# Prac_FabLab.net
KiCad netlist of a schematic drawn in Altium Designer
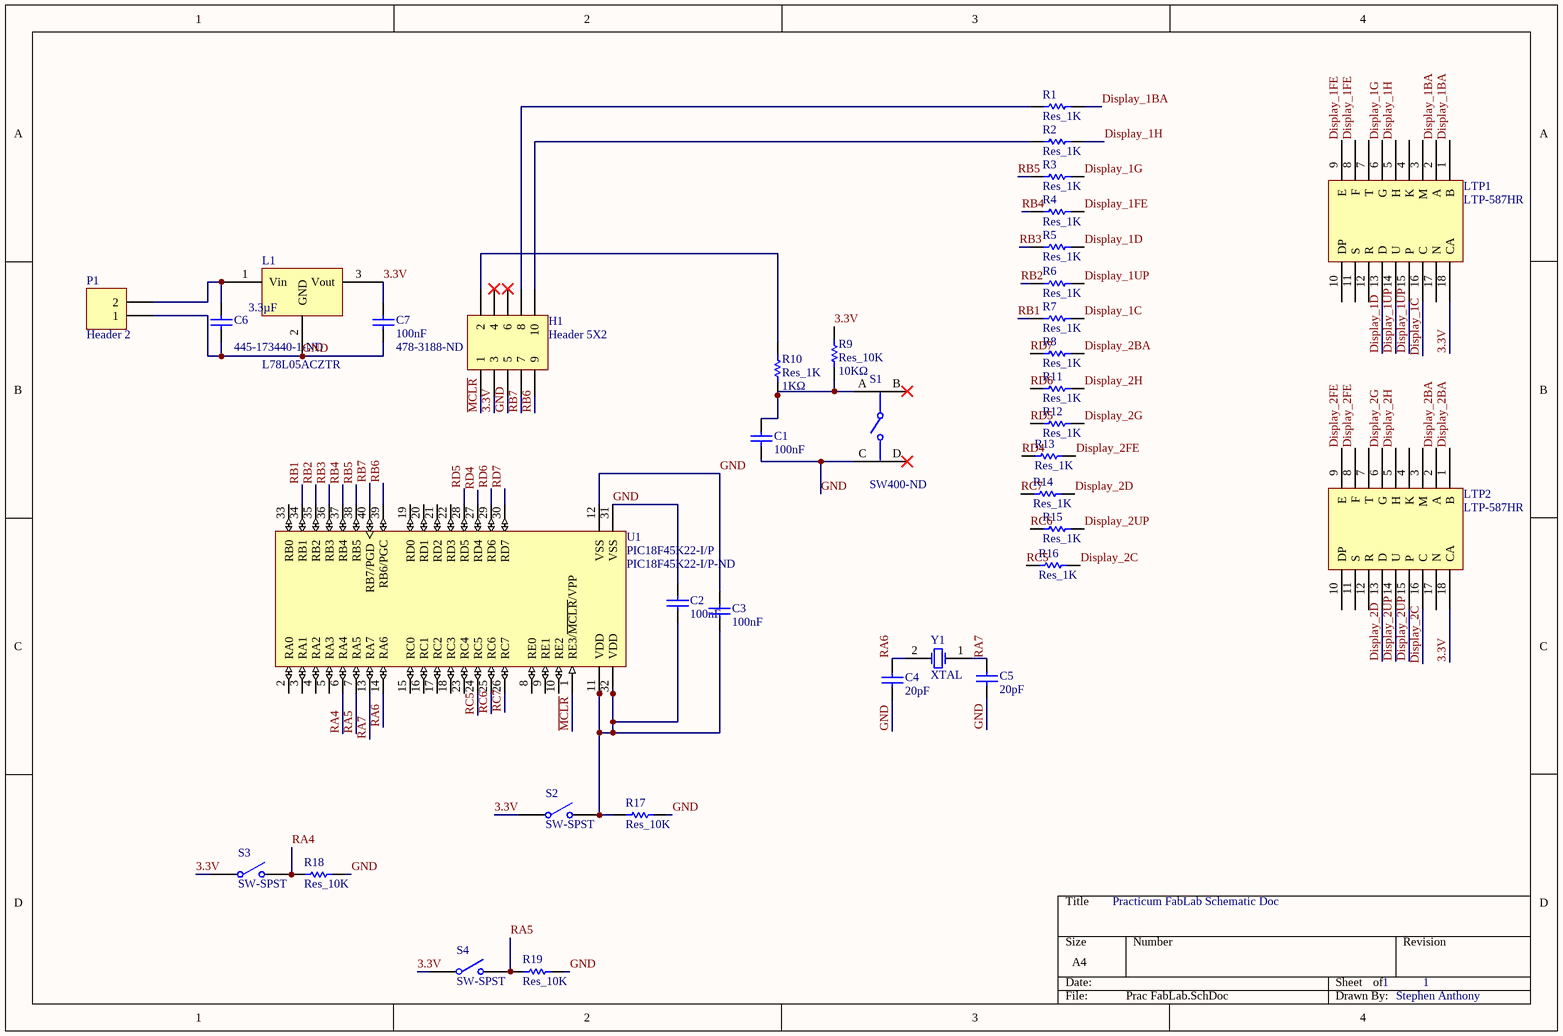
[diagram p0: Prac FabLab.SchDoc]

(export (version "E")
  (design (tool "Eeschema 10.0.6"))
  (components
    (comp (ref "C1")
      (value "100nF")
      (footprint "RADIAL_0.2")
      (description "Capacitor")
      (fields (field (name "Comment") "CAP_100nF") (field (name "PUBLISHER") "Altium Limited"))
      (libsource (lib "Schematic Components") (part "CAP_100nF"))
    )
    (comp (ref "C2")
      (value "100nF")
      (footprint "RADIAL_0.2")
      (description "Capacitor")
      (fields (field (name "Comment") "CAP_100nF") (field (name "PUBLISHER") "Altium Limited"))
      (libsource (lib "Schematic Components") (part "CAP_100nF"))
    )
    (comp (ref "C3")
      (value "100nF")
      (footprint "RADIAL_0.2")
      (description "Capacitor")
      (fields (field (name "Comment") "CAP_100nF") (field (name "PUBLISHER") "Altium Limited"))
      (libsource (lib "Schematic Components") (part "CAP_100nF"))
    )
    (comp (ref "C4")
      (value "20pF")
      (footprint "RADIAL_0.2")
      (description "Capacitor")
      (fields (field (name "PUBLISHER") "Altium Limited"))
      (libsource (lib "Patient Alarm System Altium Integrated Library of Components") (part "Capacitor"))
    )
    (comp (ref "C5")
      (value "20pF")
      (footprint "RADIAL_0.2")
      (description "Capacitor")
      (fields (field (name "PUBLISHER") "Altium Limited"))
      (libsource (lib "Patient Alarm System Altium Integrated Library of Components") (part "Capacitor"))
    )
    (comp (ref "C6")
      (value "3.3µF")
      (footprint "AXIAL_0.2")
      (description "Capacitor")
      (fields
        (field (name "SUPPLIER PART NUMBER 1") "445-173440-1-ND")
        (field (name "Comment") "CAP_3.3µF")
        (field (name "PUBLISHER") "Altium Limited")
      )
      (libsource (lib "Patient Alarm System Altium Integrated Library of Components") (part "CAP_3.3µF"))
    )
    (comp (ref "C7")
      (value "100nF")
      (footprint "AXIAL_0.2")
      (description "Capacitor")
      (fields
        (field (name "SUPPLIER PART NUMBER 1") "478-3188-ND")
        (field (name "Comment") "CAP_100nF")
        (field (name "PUBLISHER") "Altium Limited")
      )
      (libsource (lib "Patient Alarm System Altium Integrated Library of Components") (part "CAP_100nF"))
    )
    (comp (ref "H1")
      (value "Header 5X2")
      (footprint "HDR2X5")
      (description "Header, 5-Pin, Dual row")
      (fields (field (name "PUBLISHER") "Altium Limited"))
      (libsource (lib "Miscellaneous Connectors") (part "Header 5X2"))
    )
    (comp (ref "L1")
      (value "L78L05ACZTR")
      (footprint "TO-220-AB")
      (libsource (lib "Patient Alarm System Altium Integrated Library of Components") (part "L78L05ACZTR"))
    )
    (comp (ref "LTP1")
      (value "LTP-587HR")
      (footprint "LTP-587HR_DIP18")
      (libsource (lib "Patient Alarm System Altium Integrated Library of Components") (part "LTP-587HR"))
    )
    (comp (ref "LTP2")
      (value "LTP-587HR")
      (footprint "LTP-587HR_DIP18")
      (libsource (lib "Patient Alarm System Altium Integrated Library of Components") (part "LTP-587HR"))
    )
    (comp (ref "P1")
      (value "Header 2")
      (footprint "HDR1X2")
      (description "Header, 2-Pin")
      (fields (field (name "PUBLISHER") "Altium Limited"))
      (libsource (lib "Miscellaneous Connectors") (part "Header 2"))
    )
    (comp (ref "R1")
      (value "Res_1K")
      (footprint "AXIAL-0.3")
      (description "1 kOhms ±1% 0.25W, 1/4W Through Hole Resistor Axial Flame Retardant Coating, Safety Metal Film")
      (fields (field (name "PUBLISHER") "Altium Limited"))
      (libsource (lib "Patient Alarm System Altium Integrated Library of Components") (part "Res_1K"))
    )
    (comp (ref "R2")
      (value "Res_1K")
      (footprint "AXIAL-0.3")
      (description "1 kOhms ±1% 0.25W, 1/4W Through Hole Resistor Axial Flame Retardant Coating, Safety Metal Film")
      (fields (field (name "PUBLISHER") "Altium Limited"))
      (libsource (lib "Patient Alarm System Altium Integrated Library of Components") (part "Res_1K"))
    )
    (comp (ref "R3")
      (value "Res_1K")
      (footprint "AXIAL-0.3")
      (description "1 kOhms ±1% 0.25W, 1/4W Through Hole Resistor Axial Flame Retardant Coating, Safety Metal Film")
      (fields (field (name "PUBLISHER") "Altium Limited"))
      (libsource (lib "Patient Alarm System Altium Integrated Library of Components") (part "Res_1K"))
    )
    (comp (ref "R4")
      (value "Res_1K")
      (footprint "AXIAL-0.3")
      (description "1 kOhms ±1% 0.25W, 1/4W Through Hole Resistor Axial Flame Retardant Coating, Safety Metal Film")
      (fields (field (name "PUBLISHER") "Altium Limited"))
      (libsource (lib "Patient Alarm System Altium Integrated Library of Components") (part "Res_1K"))
    )
    (comp (ref "R5")
      (value "Res_1K")
      (footprint "AXIAL-0.3")
      (description "1 kOhms ±1% 0.25W, 1/4W Through Hole Resistor Axial Flame Retardant Coating, Safety Metal Film")
      (fields (field (name "PUBLISHER") "Altium Limited"))
      (libsource (lib "Patient Alarm System Altium Integrated Library of Components") (part "Res_1K"))
    )
    (comp (ref "R6")
      (value "Res_1K")
      (footprint "AXIAL-0.3")
      (description "1 kOhms ±1% 0.25W, 1/4W Through Hole Resistor Axial Flame Retardant Coating, Safety Metal Film")
      (fields (field (name "PUBLISHER") "Altium Limited"))
      (libsource (lib "Patient Alarm System Altium Integrated Library of Components") (part "Res_1K"))
    )
    (comp (ref "R7")
      (value "Res_1K")
      (footprint "AXIAL-0.3")
      (description "1 kOhms ±1% 0.25W, 1/4W Through Hole Resistor Axial Flame Retardant Coating, Safety Metal Film")
      (fields (field (name "PUBLISHER") "Altium Limited"))
      (libsource (lib "Patient Alarm System Altium Integrated Library of Components") (part "Res_1K"))
    )
    (comp (ref "R8")
      (value "Res_1K")
      (footprint "AXIAL-0.3")
      (description "1 kOhms ±1% 0.25W, 1/4W Through Hole Resistor Axial Flame Retardant Coating, Safety Metal Film")
      (fields (field (name "PUBLISHER") "Altium Limited"))
      (libsource (lib "Patient Alarm System Altium Integrated Library of Components") (part "Res_1K"))
    )
    (comp (ref "R9")
      (value "Res_10K")
      (footprint "AXIAL-0.3")
      (description "10 kOhms ±1% 0.25W, 1/4W Through Hole Resistor Axial Flame Retardant Coating, Safety Metal Film")
      (fields (field (name "ALTIUM_VALUE") "10KΩ") (field (name "PUBLISHER") "Altium Limited"))
      (libsource (lib "Schematic Components") (part "Res_10K"))
    )
    (comp (ref "R10")
      (value "Res_1K")
      (footprint "AXIAL-0.3")
      (description "1 kOhms ±1% 0.25W, 1/4W Through Hole Resistor Axial Flame Retardant Coating, Safety Metal Film")
      (fields (field (name "ALTIUM_VALUE") "1KΩ") (field (name "PUBLISHER") "Altium Limited"))
      (libsource (lib "Schematic Components") (part "Res_1K"))
    )
    (comp (ref "R11")
      (value "Res_1K")
      (footprint "AXIAL-0.3")
      (description "1 kOhms ±1% 0.25W, 1/4W Through Hole Resistor Axial Flame Retardant Coating, Safety Metal Film")
      (fields (field (name "PUBLISHER") "Altium Limited"))
      (libsource (lib "Patient Alarm System Altium Integrated Library of Components") (part "Res_1K"))
    )
    (comp (ref "R12")
      (value "Res_1K")
      (footprint "AXIAL-0.3")
      (description "1 kOhms ±1% 0.25W, 1/4W Through Hole Resistor Axial Flame Retardant Coating, Safety Metal Film")
      (fields (field (name "PUBLISHER") "Altium Limited"))
      (libsource (lib "Patient Alarm System Altium Integrated Library of Components") (part "Res_1K"))
    )
    (comp (ref "R13")
      (value "Res_1K")
      (footprint "AXIAL-0.3")
      (description "1 kOhms ±1% 0.25W, 1/4W Through Hole Resistor Axial Flame Retardant Coating, Safety Metal Film")
      (fields (field (name "PUBLISHER") "Altium Limited"))
      (libsource (lib "Patient Alarm System Altium Integrated Library of Components") (part "Res_1K"))
    )
    (comp (ref "R14")
      (value "Res_1K")
      (footprint "AXIAL-0.3")
      (description "1 kOhms ±1% 0.25W, 1/4W Through Hole Resistor Axial Flame Retardant Coating, Safety Metal Film")
      (fields (field (name "PUBLISHER") "Altium Limited"))
      (libsource (lib "Patient Alarm System Altium Integrated Library of Components") (part "Res_1K"))
    )
    (comp (ref "R15")
      (value "Res_1K")
      (footprint "AXIAL-0.3")
      (description "1 kOhms ±1% 0.25W, 1/4W Through Hole Resistor Axial Flame Retardant Coating, Safety Metal Film")
      (fields (field (name "PUBLISHER") "Altium Limited"))
      (libsource (lib "Patient Alarm System Altium Integrated Library of Components") (part "Res_1K"))
    )
    (comp (ref "R16")
      (value "Res_1K")
      (footprint "AXIAL-0.3")
      (description "1 kOhms ±1% 0.25W, 1/4W Through Hole Resistor Axial Flame Retardant Coating, Safety Metal Film")
      (fields (field (name "PUBLISHER") "Altium Limited"))
      (libsource (lib "Patient Alarm System Altium Integrated Library of Components") (part "Res_1K"))
    )
    (comp (ref "R17")
      (value "Res_10K")
      (footprint "AXIAL-0.3")
      (description "1 kOhms ±1% 0.25W, 1/4W Through Hole Resistor Axial Flame Retardant Coating, Safety Metal Film")
      (fields (field (name "PUBLISHER") "Altium Limited"))
      (libsource (lib "Patient Alarm System Altium Integrated Library of Components") (part "Res_1K"))
    )
    (comp (ref "R18")
      (value "Res_10K")
      (footprint "AXIAL-0.3")
      (description "1 kOhms ±1% 0.25W, 1/4W Through Hole Resistor Axial Flame Retardant Coating, Safety Metal Film")
      (fields (field (name "PUBLISHER") "Altium Limited"))
      (libsource (lib "Patient Alarm System Altium Integrated Library of Components") (part "Res_1K"))
    )
    (comp (ref "R19")
      (value "Res_10K")
      (footprint "AXIAL-0.3")
      (description "1 kOhms ±1% 0.25W, 1/4W Through Hole Resistor Axial Flame Retardant Coating, Safety Metal Film")
      (fields (field (name "PUBLISHER") "Altium Limited"))
      (libsource (lib "Patient Alarm System Altium Integrated Library of Components") (part "Res_1K"))
    )
    (comp (ref "S1")
      (value "~")
      (footprint "SW-SPST-1")
      (description "Tactile Switch SPST-NO Top Actuated Through Hole")
      (fields (field (name "SUPPLIER PART NUMBER 1") "SW400-ND") (field (name "PUBLISHER") "Altium Limited"))
      (libsource (lib "Schematic Components") (part "SW-SPST_B3F-1000"))
    )
    (comp (ref "S2")
      (value "SW-SPST")
      (footprint "SPST-2")
      (description "Single-Pole, Single-Throw Switch")
      (fields (field (name "PUBLISHER") "Altium Limited"))
      (libsource (lib "Miscellaneous Devices") (part "SW-SPST"))
    )
    (comp (ref "S3")
      (value "SW-SPST")
      (footprint "SPST-2")
      (description "Single-Pole, Single-Throw Switch")
      (fields (field (name "PUBLISHER") "Altium Limited"))
      (libsource (lib "Miscellaneous Devices") (part "SW-SPST"))
    )
    (comp (ref "S4")
      (value "SW-SPST")
      (footprint "SPST-2")
      (description "Single-Pole, Single-Throw Switch")
      (fields (field (name "PUBLISHER") "Altium Limited"))
      (libsource (lib "Miscellaneous Devices") (part "SW-SPST"))
    )
    (comp (ref "U1")
      (value "PIC18F45K22-I/P")
      (footprint "MCHP-PDIP-P40")
      (fields
        (field (name "MANUFACTURER") "Microchip")
        (field (name "SUPPLIER PART NUMBER 1") "PIC18F45K22-I/P-ND")
      )
      (libsource (lib "Schematic Components") (part "PIC18F45K22-I/P"))
    )
    (comp (ref "Y1")
      (value "XTAL")
      (footprint "R38")
      (description "Crystal Oscillator")
      (fields (field (name "PUBLISHER") "Altium Limited"))
      (libsource (lib "Miscellaneous Devices") (part "XTAL"))
    )
  )
  (nets
    (net (code "1") (name "/3.3V") (class "Default")
      (node (ref "C7") (pin "2") (pinfunction "2_2") (pintype "passive"))
      (node (ref "H1") (pin "3") (pinfunction "3_3") (pintype "passive"))
      (node (ref "L1") (pin "3") (pinfunction "Vout_3") (pintype "power_in"))
      (node (ref "LTP1") (pin "18") (pinfunction "CA_18") (pintype "power_in"))
      (node (ref "LTP2") (pin "18") (pinfunction "CA_18") (pintype "power_in"))
      (node (ref "R9") (pin "2") (pinfunction "2_2") (pintype "passive"))
      (node (ref "S2") (pin "1") (pinfunction "COMMON_1") (pintype "passive"))
      (node (ref "S3") (pin "1") (pinfunction "COMMON_1") (pintype "passive"))
      (node (ref "S4") (pin "1") (pinfunction "COMMON_1") (pintype "passive"))
    )
    (net (code "2") (name "/Display_1BA") (class "Default")
      (node (ref "LTP1") (pin "1") (pinfunction "B_1") (pintype "passive"))
      (node (ref "LTP1") (pin "2") (pinfunction "A_2") (pintype "passive"))
      (node (ref "R1") (pin "2") (pinfunction "2_2") (pintype "passive"))
    )
    (net (code "3") (name "/Display_1C") (class "Default")
      (node (ref "LTP1") (pin "16") (pinfunction "C_16") (pintype "passive"))
      (node (ref "R7") (pin "2") (pinfunction "2_2") (pintype "passive"))
    )
    (net (code "4") (name "/Display_1D") (class "Default")
      (node (ref "LTP1") (pin "13") (pinfunction "D_13") (pintype "passive"))
      (node (ref "R5") (pin "2") (pinfunction "2_2") (pintype "passive"))
    )
    (net (code "5") (name "/Display_1FE") (class "Default")
      (node (ref "LTP1") (pin "8") (pinfunction "F_8") (pintype "passive"))
      (node (ref "LTP1") (pin "9") (pinfunction "E_9") (pintype "passive"))
      (node (ref "R4") (pin "2") (pinfunction "2_2") (pintype "passive"))
    )
    (net (code "6") (name "/Display_1G") (class "Default")
      (node (ref "LTP1") (pin "6") (pinfunction "G_6") (pintype "passive"))
      (node (ref "R3") (pin "2") (pinfunction "2_2") (pintype "passive"))
    )
    (net (code "7") (name "/Display_1H") (class "Default")
      (node (ref "LTP1") (pin "5") (pinfunction "H_5") (pintype "passive"))
      (node (ref "R2") (pin "2") (pinfunction "2_2") (pintype "passive"))
    )
    (net (code "8") (name "/Display_1UP") (class "Default")
      (node (ref "LTP1") (pin "14") (pinfunction "U_14") (pintype "passive"))
      (node (ref "LTP1") (pin "15") (pinfunction "P_15") (pintype "passive"))
      (node (ref "R6") (pin "2") (pinfunction "2_2") (pintype "passive"))
    )
    (net (code "9") (name "/Display_2BA") (class "Default")
      (node (ref "LTP2") (pin "1") (pinfunction "B_1") (pintype "passive"))
      (node (ref "LTP2") (pin "2") (pinfunction "A_2") (pintype "passive"))
      (node (ref "R8") (pin "2") (pinfunction "2_2") (pintype "passive"))
    )
    (net (code "10") (name "/Display_2C") (class "Default")
      (node (ref "LTP2") (pin "16") (pinfunction "C_16") (pintype "passive"))
      (node (ref "R16") (pin "2") (pinfunction "2_2") (pintype "passive"))
    )
    (net (code "11") (name "/Display_2D") (class "Default")
      (node (ref "LTP2") (pin "13") (pinfunction "D_13") (pintype "passive"))
      (node (ref "R14") (pin "2") (pinfunction "2_2") (pintype "passive"))
    )
    (net (code "12") (name "/Display_2FE") (class "Default")
      (node (ref "LTP2") (pin "8") (pinfunction "F_8") (pintype "passive"))
      (node (ref "LTP2") (pin "9") (pinfunction "E_9") (pintype "passive"))
      (node (ref "R13") (pin "2") (pinfunction "2_2") (pintype "passive"))
    )
    (net (code "13") (name "/Display_2G") (class "Default")
      (node (ref "LTP2") (pin "6") (pinfunction "G_6") (pintype "passive"))
      (node (ref "R12") (pin "2") (pinfunction "2_2") (pintype "passive"))
    )
    (net (code "14") (name "/Display_2H") (class "Default")
      (node (ref "LTP2") (pin "5") (pinfunction "H_5") (pintype "passive"))
      (node (ref "R11") (pin "2") (pinfunction "2_2") (pintype "passive"))
    )
    (net (code "15") (name "/Display_2UP") (class "Default")
      (node (ref "LTP2") (pin "14") (pinfunction "U_14") (pintype "passive"))
      (node (ref "LTP2") (pin "15") (pinfunction "P_15") (pintype "passive"))
      (node (ref "R15") (pin "2") (pinfunction "2_2") (pintype "passive"))
    )
    (net (code "16") (name "/GND") (class "Default")
      (node (ref "C1") (pin "2") (pinfunction "2_2") (pintype "passive"))
      (node (ref "C2") (pin "2") (pinfunction "2_2") (pintype "passive"))
      (node (ref "C3") (pin "2") (pinfunction "2_2") (pintype "passive"))
      (node (ref "C4") (pin "1") (pinfunction "1_1") (pintype "passive"))
      (node (ref "C5") (pin "1") (pinfunction "1_1") (pintype "passive"))
      (node (ref "C6") (pin "1") (pinfunction "1_1") (pintype "passive"))
      (node (ref "C7") (pin "1") (pinfunction "1_1") (pintype "passive"))
      (node (ref "H1") (pin "5") (pinfunction "5_5") (pintype "passive"))
      (node (ref "L1") (pin "2") (pinfunction "GND_2") (pintype "power_in"))
      (node (ref "P1") (pin "1") (pinfunction "1_1") (pintype "passive"))
      (node (ref "R17") (pin "2") (pinfunction "2_2") (pintype "passive"))
      (node (ref "R18") (pin "2") (pinfunction "2_2") (pintype "passive"))
      (node (ref "R19") (pin "2") (pinfunction "2_2") (pintype "passive"))
      (node (ref "S1") (pin "C") (pinfunction "NO_C") (pintype "passive"))
      (node (ref "U1") (pin "12") (pinfunction "VSS_12") (pintype "power_in"))
      (node (ref "U1") (pin "31") (pinfunction "VSS_31") (pintype "power_in"))
    )
    (net (code "17") (name "/RA4") (class "Default")
      (node (ref "R18") (pin "1") (pinfunction "1_1") (pintype "passive"))
      (node (ref "S3") (pin "2") (pinfunction "NO_2") (pintype "passive"))
      (node (ref "U1") (pin "6") (pinfunction "RA4_6") (pintype "bidirectional"))
    )
    (net (code "18") (name "/RA5") (class "Default")
      (node (ref "R19") (pin "1") (pinfunction "1_1") (pintype "passive"))
      (node (ref "S4") (pin "2") (pinfunction "NO_2") (pintype "passive"))
      (node (ref "U1") (pin "7") (pinfunction "RA5_7") (pintype "bidirectional"))
    )
    (net (code "19") (name "/RA6") (class "Default")
      (node (ref "C4") (pin "2") (pinfunction "2_2") (pintype "passive"))
      (node (ref "U1") (pin "14") (pinfunction "RA6_14") (pintype "bidirectional"))
      (node (ref "Y1") (pin "2") (pinfunction "OSC2_2") (pintype "passive"))
    )
    (net (code "20") (name "/RA7") (class "Default")
      (node (ref "C5") (pin "2") (pinfunction "2_2") (pintype "passive"))
      (node (ref "U1") (pin "13") (pinfunction "RA7_13") (pintype "bidirectional"))
      (node (ref "Y1") (pin "1") (pinfunction "OSC1_1") (pintype "passive"))
    )
    (net (code "21") (name "/RB1") (class "Default")
      (node (ref "R7") (pin "1") (pinfunction "1_1") (pintype "passive"))
      (node (ref "U1") (pin "34") (pinfunction "RB1_34") (pintype "bidirectional"))
    )
    (net (code "22") (name "/RB2") (class "Default")
      (node (ref "R6") (pin "1") (pinfunction "1_1") (pintype "passive"))
      (node (ref "U1") (pin "35") (pinfunction "RB2_35") (pintype "bidirectional"))
    )
    (net (code "23") (name "/RB3") (class "Default")
      (node (ref "R5") (pin "1") (pinfunction "1_1") (pintype "passive"))
      (node (ref "U1") (pin "36") (pinfunction "RB3_36") (pintype "bidirectional"))
    )
    (net (code "24") (name "/RB4") (class "Default")
      (node (ref "R4") (pin "1") (pinfunction "1_1") (pintype "passive"))
      (node (ref "U1") (pin "37") (pinfunction "RB4_37") (pintype "bidirectional"))
    )
    (net (code "25") (name "/RB5") (class "Default")
      (node (ref "R3") (pin "1") (pinfunction "1_1") (pintype "passive"))
      (node (ref "U1") (pin "38") (pinfunction "RB5_38") (pintype "bidirectional"))
    )
    (net (code "26") (name "/RB6") (class "Default")
      (node (ref "H1") (pin "9") (pinfunction "9_9") (pintype "passive"))
      (node (ref "U1") (pin "39") (pinfunction "RB6/PGC_39") (pintype "bidirectional"))
    )
    (net (code "27") (name "/RB7") (class "Default")
      (node (ref "H1") (pin "7") (pinfunction "7_7") (pintype "passive"))
      (node (ref "U1") (pin "40") (pinfunction "RB7/PGD_40") (pintype "bidirectional"))
    )
    (net (code "28") (name "/RC5") (class "Default")
      (node (ref "R16") (pin "1") (pinfunction "1_1") (pintype "passive"))
      (node (ref "U1") (pin "24") (pinfunction "RC5_24") (pintype "bidirectional"))
    )
    (net (code "29") (name "/RC6") (class "Default")
      (node (ref "R15") (pin "1") (pinfunction "1_1") (pintype "passive"))
      (node (ref "U1") (pin "25") (pinfunction "RC6_25") (pintype "bidirectional"))
    )
    (net (code "30") (name "/RC7") (class "Default")
      (node (ref "R14") (pin "1") (pinfunction "1_1") (pintype "passive"))
      (node (ref "U1") (pin "26") (pinfunction "RC7_26") (pintype "bidirectional"))
    )
    (net (code "31") (name "/RD4") (class "Default")
      (node (ref "R13") (pin "1") (pinfunction "1_1") (pintype "passive"))
      (node (ref "U1") (pin "27") (pinfunction "RD4_27") (pintype "bidirectional"))
    )
    (net (code "32") (name "/RD5") (class "Default")
      (node (ref "R12") (pin "1") (pinfunction "1_1") (pintype "passive"))
      (node (ref "U1") (pin "28") (pinfunction "RD5_28") (pintype "bidirectional"))
    )
    (net (code "33") (name "/RD6") (class "Default")
      (node (ref "R11") (pin "1") (pinfunction "1_1") (pintype "passive"))
      (node (ref "U1") (pin "29") (pinfunction "RD6_29") (pintype "bidirectional"))
    )
    (net (code "34") (name "/RD7") (class "Default")
      (node (ref "R8") (pin "1") (pinfunction "1_1") (pintype "passive"))
      (node (ref "U1") (pin "30") (pinfunction "RD7_30") (pintype "bidirectional"))
    )
    (net (code "35") (name "/~{MCLR}") (class "Default")
      (node (ref "H1") (pin "1") (pinfunction "1_1") (pintype "passive"))
      (node (ref "U1") (pin "1") (pinfunction "RE3/~{MCLR}/VPP_1") (pintype "input"))
    )
    (net (code "36") (name "Net-(C1-Pad1)") (class "Default")
      (node (ref "C1") (pin "1") (pinfunction "1_1") (pintype "passive"))
      (node (ref "R10") (pin "1") (pinfunction "1_1") (pintype "passive"))
      (node (ref "R9") (pin "1") (pinfunction "1_1") (pintype "passive"))
      (node (ref "S1") (pin "A") (pinfunction "COMMON_A") (pintype "passive"))
    )
    (net (code "37") (name "Net-(H1-Pad2)") (class "Default")
      (node (ref "H1") (pin "2") (pinfunction "2_2") (pintype "passive"))
      (node (ref "R10") (pin "2") (pinfunction "2_2") (pintype "passive"))
    )
    (net (code "38") (name "Net-(H1-Pad8)") (class "Default")
      (node (ref "H1") (pin "8") (pinfunction "8_8") (pintype "passive"))
      (node (ref "R1") (pin "1") (pinfunction "1_1") (pintype "passive"))
    )
    (net (code "39") (name "Net-(H1-Pad10)") (class "Default")
      (node (ref "H1") (pin "10") (pinfunction "10_10") (pintype "passive"))
      (node (ref "R2") (pin "1") (pinfunction "1_1") (pintype "passive"))
    )
    (net (code "40") (name "Net-(L1-Vin)") (class "Default")
      (node (ref "C6") (pin "2") (pinfunction "2_2") (pintype "passive"))
      (node (ref "L1") (pin "1") (pinfunction "Vin_1") (pintype "power_in"))
      (node (ref "P1") (pin "2") (pinfunction "2_2") (pintype "passive"))
    )
    (net (code "41") (name "Net-(S2-NO)") (class "Default")
      (node (ref "C2") (pin "1") (pinfunction "1_1") (pintype "passive"))
      (node (ref "C3") (pin "1") (pinfunction "1_1") (pintype "passive"))
      (node (ref "R17") (pin "1") (pinfunction "1_1") (pintype "passive"))
      (node (ref "S2") (pin "2") (pinfunction "NO_2") (pintype "passive"))
      (node (ref "U1") (pin "11") (pinfunction "VDD_11") (pintype "power_in"))
      (node (ref "U1") (pin "32") (pinfunction "VDD_32") (pintype "power_in"))
    )
    (net (code "42") (name "unconnected-(H1-Pad4)") (class "Default")
      (node (ref "H1") (pin "4") (pinfunction "4_4") (pintype "passive+no_connect"))
    )
    (net (code "43") (name "unconnected-(H1-Pad6)") (class "Default")
      (node (ref "H1") (pin "6") (pinfunction "6_6") (pintype "passive+no_connect"))
    )
    (net (code "44") (name "unconnected-(LTP1-DP-Pad10)") (class "Default")
      (node (ref "LTP1") (pin "10") (pinfunction "DP_10") (pintype "passive"))
    )
    (net (code "45") (name "unconnected-(LTP1-K-Pad4)") (class "Default")
      (node (ref "LTP1") (pin "4") (pinfunction "K_4") (pintype "passive"))
    )
    (net (code "46") (name "unconnected-(LTP1-M-Pad3)") (class "Default")
      (node (ref "LTP1") (pin "3") (pinfunction "M_3") (pintype "passive"))
    )
    (net (code "47") (name "unconnected-(LTP1-N-Pad17)") (class "Default")
      (node (ref "LTP1") (pin "17") (pinfunction "N_17") (pintype "passive"))
    )
    (net (code "48") (name "unconnected-(LTP1-R-Pad12)") (class "Default")
      (node (ref "LTP1") (pin "12") (pinfunction "R_12") (pintype "passive"))
    )
    (net (code "49") (name "unconnected-(LTP1-S-Pad11)") (class "Default")
      (node (ref "LTP1") (pin "11") (pinfunction "S_11") (pintype "passive"))
    )
    (net (code "50") (name "unconnected-(LTP1-T-Pad7)") (class "Default")
      (node (ref "LTP1") (pin "7") (pinfunction "T_7") (pintype "passive"))
    )
    (net (code "51") (name "unconnected-(LTP2-DP-Pad10)") (class "Default")
      (node (ref "LTP2") (pin "10") (pinfunction "DP_10") (pintype "passive"))
    )
    (net (code "52") (name "unconnected-(LTP2-K-Pad4)") (class "Default")
      (node (ref "LTP2") (pin "4") (pinfunction "K_4") (pintype "passive"))
    )
    (net (code "53") (name "unconnected-(LTP2-M-Pad3)") (class "Default")
      (node (ref "LTP2") (pin "3") (pinfunction "M_3") (pintype "passive"))
    )
    (net (code "54") (name "unconnected-(LTP2-N-Pad17)") (class "Default")
      (node (ref "LTP2") (pin "17") (pinfunction "N_17") (pintype "passive"))
    )
    (net (code "55") (name "unconnected-(LTP2-R-Pad12)") (class "Default")
      (node (ref "LTP2") (pin "12") (pinfunction "R_12") (pintype "passive"))
    )
    (net (code "56") (name "unconnected-(LTP2-S-Pad11)") (class "Default")
      (node (ref "LTP2") (pin "11") (pinfunction "S_11") (pintype "passive"))
    )
    (net (code "57") (name "unconnected-(LTP2-T-Pad7)") (class "Default")
      (node (ref "LTP2") (pin "7") (pinfunction "T_7") (pintype "passive"))
    )
    (net (code "58") (name "unconnected-(S1-COMMON-PadB)") (class "Default")
      (node (ref "S1") (pin "B") (pinfunction "COMMON_B") (pintype "passive+no_connect"))
    )
    (net (code "59") (name "unconnected-(S1-NO-PadD)") (class "Default")
      (node (ref "S1") (pin "D") (pinfunction "NO_D") (pintype "passive+no_connect"))
    )
    (net (code "60") (name "unconnected-(U1-RA0-Pad2)") (class "Default")
      (node (ref "U1") (pin "2") (pinfunction "RA0_2") (pintype "bidirectional"))
    )
    (net (code "61") (name "unconnected-(U1-RA1-Pad3)") (class "Default")
      (node (ref "U1") (pin "3") (pinfunction "RA1_3") (pintype "bidirectional"))
    )
    (net (code "62") (name "unconnected-(U1-RA2-Pad4)") (class "Default")
      (node (ref "U1") (pin "4") (pinfunction "RA2_4") (pintype "bidirectional"))
    )
    (net (code "63") (name "unconnected-(U1-RA3-Pad5)") (class "Default")
      (node (ref "U1") (pin "5") (pinfunction "RA3_5") (pintype "bidirectional"))
    )
    (net (code "64") (name "unconnected-(U1-RB0-Pad33)") (class "Default")
      (node (ref "U1") (pin "33") (pinfunction "RB0_33") (pintype "bidirectional"))
    )
    (net (code "65") (name "unconnected-(U1-RC0-Pad15)") (class "Default")
      (node (ref "U1") (pin "15") (pinfunction "RC0_15") (pintype "bidirectional"))
    )
    (net (code "66") (name "unconnected-(U1-RC1-Pad16)") (class "Default")
      (node (ref "U1") (pin "16") (pinfunction "RC1_16") (pintype "bidirectional"))
    )
    (net (code "67") (name "unconnected-(U1-RC2-Pad17)") (class "Default")
      (node (ref "U1") (pin "17") (pinfunction "RC2_17") (pintype "bidirectional"))
    )
    (net (code "68") (name "unconnected-(U1-RC3-Pad18)") (class "Default")
      (node (ref "U1") (pin "18") (pinfunction "RC3_18") (pintype "bidirectional"))
    )
    (net (code "69") (name "unconnected-(U1-RC4-Pad23)") (class "Default")
      (node (ref "U1") (pin "23") (pinfunction "RC4_23") (pintype "bidirectional"))
    )
    (net (code "70") (name "unconnected-(U1-RD0-Pad19)") (class "Default")
      (node (ref "U1") (pin "19") (pinfunction "RD0_19") (pintype "bidirectional"))
    )
    (net (code "71") (name "unconnected-(U1-RD1-Pad20)") (class "Default")
      (node (ref "U1") (pin "20") (pinfunction "RD1_20") (pintype "bidirectional"))
    )
    (net (code "72") (name "unconnected-(U1-RD2-Pad21)") (class "Default")
      (node (ref "U1") (pin "21") (pinfunction "RD2_21") (pintype "bidirectional"))
    )
    (net (code "73") (name "unconnected-(U1-RD3-Pad22)") (class "Default")
      (node (ref "U1") (pin "22") (pinfunction "RD3_22") (pintype "bidirectional"))
    )
    (net (code "74") (name "unconnected-(U1-RE0-Pad8)") (class "Default")
      (node (ref "U1") (pin "8") (pinfunction "RE0_8") (pintype "bidirectional"))
    )
    (net (code "75") (name "unconnected-(U1-RE1-Pad9)") (class "Default")
      (node (ref "U1") (pin "9") (pinfunction "RE1_9") (pintype "bidirectional"))
    )
    (net (code "76") (name "unconnected-(U1-RE2-Pad10)") (class "Default")
      (node (ref "U1") (pin "10") (pinfunction "RE2_10") (pintype "bidirectional"))
    )
  )
)
